# 5050_Breakout.net
KiCad netlist of a schematic drawn in Altium Designer
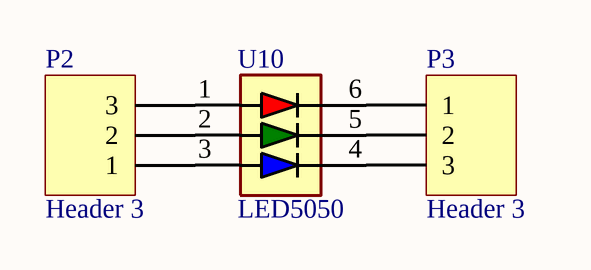
[diagram p0: 5050 Breakout.SchDoc]

(export (version "E")
  (design (tool "Eeschema 10.0.6"))
  (components
    (comp (ref "P2")
      (value "Header 3")
      (footprint "HDR1X3")
      (description "Header, 3-Pin")
      (fields (field (name "PUBLISHER") "Altium Limited"))
      (libsource (lib "Miscellaneous Connectors") (part "Header 3"))
    )
    (comp (ref "P3")
      (value "Header 3")
      (footprint "HDR1X3")
      (description "Header, 3-Pin")
      (fields (field (name "PUBLISHER") "Altium Limited"))
      (libsource (lib "") (part "Header 3_1"))
    )
    (comp (ref "U10")
      (value "LED5050")
      (footprint "SOP6")
      (description "Surfage Mount RGB LED Pack")
      (libsource (lib "Connectors") (part "LED5050"))
    )
  )
  (nets
    (net (code "1") (name "Net-(P2-Pad1)") (class "Default")
      (node (ref "P2") (pin "1") (pinfunction "1_1") (pintype "passive"))
      (node (ref "U10") (pin "3") (pintype "passive"))
    )
    (net (code "2") (name "Net-(P2-Pad2)") (class "Default")
      (node (ref "P2") (pin "2") (pinfunction "2_2") (pintype "passive"))
      (node (ref "U10") (pin "2") (pintype "passive"))
    )
    (net (code "3") (name "Net-(P2-Pad3)") (class "Default")
      (node (ref "P2") (pin "3") (pinfunction "3_3") (pintype "passive"))
      (node (ref "U10") (pin "1") (pintype "passive"))
    )
    (net (code "4") (name "Net-(P3-Pad1)") (class "Default")
      (node (ref "P3") (pin "1") (pinfunction "1_1") (pintype "passive"))
      (node (ref "U10") (pin "6") (pintype "passive"))
    )
    (net (code "5") (name "Net-(P3-Pad2)") (class "Default")
      (node (ref "P3") (pin "2") (pinfunction "2_2") (pintype "passive"))
      (node (ref "U10") (pin "5") (pintype "passive"))
    )
    (net (code "6") (name "Net-(P3-Pad3)") (class "Default")
      (node (ref "P3") (pin "3") (pinfunction "3_3") (pintype "passive"))
      (node (ref "U10") (pin "4") (pintype "passive"))
    )
  )
)
